# nigme3_Potentiom_tres.net
KiCad netlist of a schematic drawn in Altium Designer
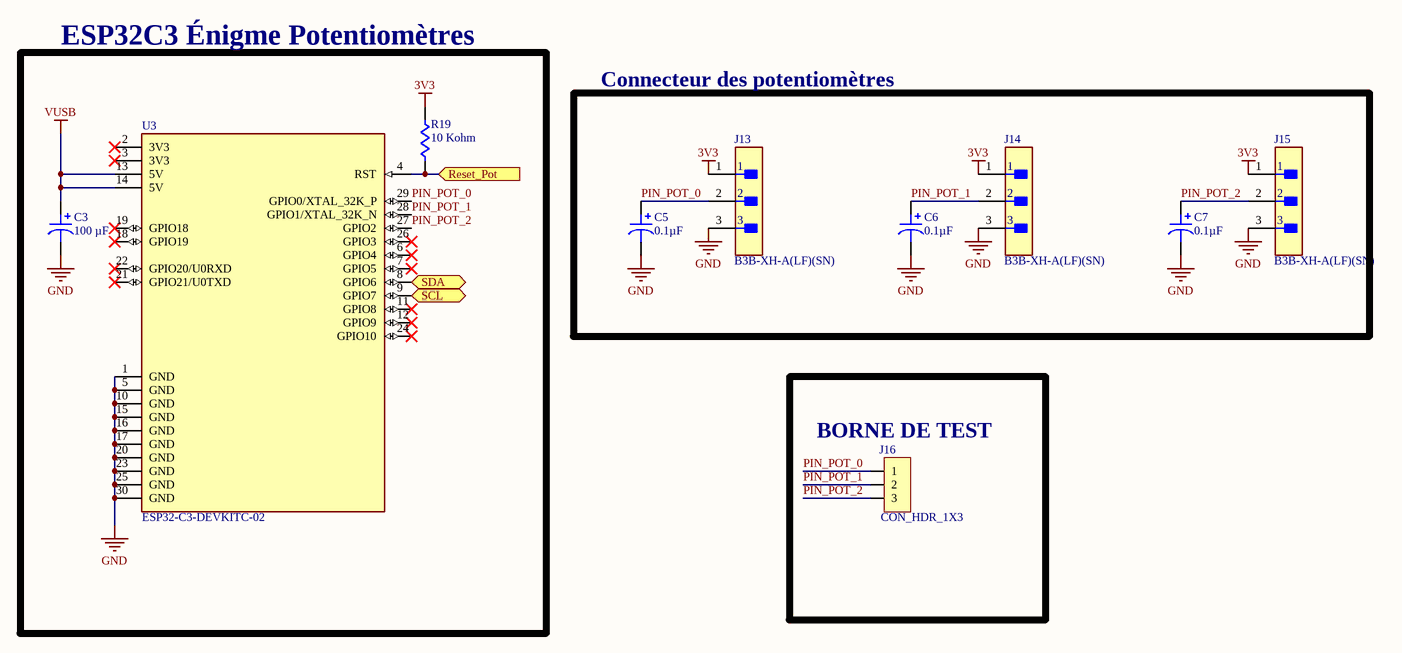
[diagram p0: Énigme3_Potentiomètres.SchDoc]

(export (version "E")
  (design (tool "Eeschema 10.0.6"))
  (components
    (comp (ref "C3")
      (value "100 µF")
      (footprint "CAP AL TH D8 L3.5 H12.5")
      (description "CAP ALUM 100UF 20% 50V RADIAL")
      (fields (field (name "PART NUMBER") "860020674015") (field (name "MANUFACTURER") "Würth Elektronik"))
      (libsource (lib "Celestial Altium Library - altium_library") (part "Polarised Capacitor"))
    )
    (comp (ref "C5")
      (value "0.1µF")
      (footprint "CAP TH ALUM ELEC D5.00mm S2.00mm H12.00mm")
      (description "CAP ALUM 0.1UF 10% 100V RADIAL")
      (fields (field (name "PART NUMBER") "UKL2A0R1KDD") (field (name "MANUFACTURER") "Nichicon"))
      (libsource (lib "Celestial Altium Library - altium_library") (part "Polarised Capacitor"))
    )
    (comp (ref "C6")
      (value "0.1µF")
      (footprint "CAP TH ALUM ELEC D5.00mm S2.00mm H12.00mm")
      (description "CAP ALUM 0.1UF 10% 100V RADIAL")
      (fields (field (name "PART NUMBER") "UKL2A0R1KDD") (field (name "MANUFACTURER") "Nichicon"))
      (libsource (lib "Celestial Altium Library - altium_library") (part "Polarised Capacitor"))
    )
    (comp (ref "C7")
      (value "0.1µF")
      (footprint "CAP TH ALUM ELEC D5.00mm S2.00mm H12.00mm")
      (description "CAP ALUM 0.1UF 10% 100V RADIAL")
      (fields (field (name "PART NUMBER") "UKL2A0R1KDD") (field (name "MANUFACTURER") "Nichicon"))
      (libsource (lib "Celestial Altium Library - altium_library") (part "Polarised Capacitor"))
    )
    (comp (ref "J13")
      (value "B3B-XH-A(LF)(SN)")
      (footprint "FP-B3B-XH-A_LF_SN-MFG")
      (description "CONN HEADER VERT 3POS 2.5MM")
      (libsource (lib "Altium Content Vault") (part "0d3f023dd272f625e17a2be33dea85f"))
    )
    (comp (ref "J14")
      (value "B3B-XH-A(LF)(SN)")
      (footprint "FP-B3B-XH-A_LF_SN-MFG")
      (description "CONN HEADER VERT 3POS 2.5MM")
      (libsource (lib "Altium Content Vault") (part "0d3f023dd272f625e17a2be33dea85f"))
    )
    (comp (ref "J15")
      (value "B3B-XH-A(LF)(SN)")
      (footprint "FP-B3B-XH-A_LF_SN-MFG")
      (description "CONN HEADER VERT 3POS 2.5MM")
      (libsource (lib "Altium Content Vault") (part "0d3f023dd272f625e17a2be33dea85f"))
    )
    (comp (ref "J16")
      (value "CON_HDR_1X3")
      (footprint "CON_HDR_1x3")
      (description "CON - Header 1x3 pins-100Mils - TH")
      (fields (field (name "SOURCE") "CEGEP_SHERBROOKE_TGE_LIBRARY.SchLib"))
      (libsource (lib "Cegep de Sherbrooke") (part "CON_HDR_1X3"))
    )
    (comp (ref "R19")
      (value "10 Kohm")
      (footprint "Res_Template")
      (description "Custom Semiconductor Resistor")
      (libsource (lib "Schlib1") (part "470 ohm"))
    )
    (comp (ref "U3")
      (value "ESP32-C3-DEVKITC-02")
      (footprint "XCVR_ESP32-C3-DEVKITC-02")
      (fields (field (name "MP") "ESP32-C3-DevKitC-02") (field (name "MF") "Espressif Systems"))
      (libsource (lib "ESP32-C3-DEVKITC-02") (part "ESP32-C3-DEVKITC-02"))
    )
  )
  (nets
    (net (code "1") (name "/PIN_POT_0") (class "Default")
      (node (ref "C5") (pin "1") (pinfunction "1_1") (pintype "passive"))
      (node (ref "J13") (pin "2") (pinfunction "2_2") (pintype "passive"))
      (node (ref "J16") (pin "1") (pinfunction "1_1") (pintype "passive"))
      (node (ref "U3") (pin "29") (pinfunction "GPIO0/XTAL_32K_P_29") (pintype "bidirectional"))
    )
    (net (code "2") (name "/PIN_POT_1") (class "Default")
      (node (ref "C6") (pin "1") (pinfunction "1_1") (pintype "passive"))
      (node (ref "J14") (pin "2") (pinfunction "2_2") (pintype "passive"))
      (node (ref "J16") (pin "2") (pinfunction "2_2") (pintype "passive"))
      (node (ref "U3") (pin "28") (pinfunction "GPIO1/XTAL_32K_N_28") (pintype "bidirectional"))
    )
    (net (code "3") (name "/PIN_POT_2") (class "Default")
      (node (ref "C7") (pin "1") (pinfunction "1_1") (pintype "passive"))
      (node (ref "J15") (pin "2") (pinfunction "2_2") (pintype "passive"))
      (node (ref "J16") (pin "3") (pinfunction "3_3") (pintype "passive"))
      (node (ref "U3") (pin "27") (pinfunction "GPIO2_27") (pintype "bidirectional"))
    )
    (net (code "4") (name "/Reset_Pot") (class "Default")
      (node (ref "R19") (pin "1") (pinfunction "1_1") (pintype "passive"))
      (node (ref "U3") (pin "4") (pinfunction "RST_4") (pintype "input"))
    )
    (net (code "5") (name "/SCL") (class "Default")
      (node (ref "U3") (pin "9") (pinfunction "GPIO7_9") (pintype "bidirectional"))
    )
    (net (code "6") (name "/SDA") (class "Default")
      (node (ref "U3") (pin "8") (pinfunction "GPIO6_8") (pintype "bidirectional"))
    )
    (net (code "7") (name "3V3") (class "Default")
      (node (ref "J13") (pin "1") (pinfunction "1_1") (pintype "passive"))
      (node (ref "J14") (pin "1") (pinfunction "1_1") (pintype "passive"))
      (node (ref "J15") (pin "1") (pinfunction "1_1") (pintype "passive"))
      (node (ref "R19") (pin "2") (pinfunction "2_2") (pintype "passive"))
    )
    (net (code "8") (name "GND") (class "Default")
      (node (ref "C3") (pin "2") (pinfunction "2_2") (pintype "passive"))
      (node (ref "C5") (pin "2") (pinfunction "2_2") (pintype "passive"))
      (node (ref "C6") (pin "2") (pinfunction "2_2") (pintype "passive"))
      (node (ref "C7") (pin "2") (pinfunction "2_2") (pintype "passive"))
      (node (ref "J13") (pin "3") (pinfunction "3_3") (pintype "passive"))
      (node (ref "J14") (pin "3") (pinfunction "3_3") (pintype "passive"))
      (node (ref "J15") (pin "3") (pinfunction "3_3") (pintype "passive"))
      (node (ref "U3") (pin "1") (pinfunction "GND_1") (pintype "power_in"))
      (node (ref "U3") (pin "10") (pinfunction "GND_10") (pintype "power_in"))
      (node (ref "U3") (pin "15") (pinfunction "GND_15") (pintype "power_in"))
      (node (ref "U3") (pin "16") (pinfunction "GND_16") (pintype "power_in"))
      (node (ref "U3") (pin "17") (pinfunction "GND_17") (pintype "power_in"))
      (node (ref "U3") (pin "20") (pinfunction "GND_20") (pintype "power_in"))
      (node (ref "U3") (pin "23") (pinfunction "GND_23") (pintype "power_in"))
      (node (ref "U3") (pin "25") (pinfunction "GND_25") (pintype "power_in"))
      (node (ref "U3") (pin "30") (pinfunction "GND_30") (pintype "power_in"))
      (node (ref "U3") (pin "5") (pinfunction "GND_5") (pintype "power_in"))
    )
    (net (code "9") (name "VUSB") (class "Default")
      (node (ref "C3") (pin "1") (pinfunction "1_1") (pintype "passive"))
      (node (ref "U3") (pin "13") (pinfunction "5V_13") (pintype "power_in"))
      (node (ref "U3") (pin "14") (pinfunction "5V_14") (pintype "power_in"))
    )
    (net (code "10") (name "unconnected-(U3-3V3-Pad2)") (class "Default")
      (node (ref "U3") (pin "2") (pinfunction "3V3_2") (pintype "power_in+no_connect"))
    )
    (net (code "11") (name "unconnected-(U3-3V3-Pad3)") (class "Default")
      (node (ref "U3") (pin "3") (pinfunction "3V3_3") (pintype "power_in+no_connect"))
    )
    (net (code "12") (name "unconnected-(U3-GPIO3-Pad26)") (class "Default")
      (node (ref "U3") (pin "26") (pinfunction "GPIO3_26") (pintype "bidirectional+no_connect"))
    )
    (net (code "13") (name "unconnected-(U3-GPIO4-Pad6)") (class "Default")
      (node (ref "U3") (pin "6") (pinfunction "GPIO4_6") (pintype "bidirectional+no_connect"))
    )
    (net (code "14") (name "unconnected-(U3-GPIO5-Pad7)") (class "Default")
      (node (ref "U3") (pin "7") (pinfunction "GPIO5_7") (pintype "bidirectional+no_connect"))
    )
    (net (code "15") (name "unconnected-(U3-GPIO8-Pad11)") (class "Default")
      (node (ref "U3") (pin "11") (pinfunction "GPIO8_11") (pintype "bidirectional+no_connect"))
    )
    (net (code "16") (name "unconnected-(U3-GPIO9-Pad12)") (class "Default")
      (node (ref "U3") (pin "12") (pinfunction "GPIO9_12") (pintype "bidirectional+no_connect"))
    )
    (net (code "17") (name "unconnected-(U3-GPIO10-Pad24)") (class "Default")
      (node (ref "U3") (pin "24") (pinfunction "GPIO10_24") (pintype "bidirectional+no_connect"))
    )
    (net (code "18") (name "unconnected-(U3-GPIO18-Pad19)") (class "Default")
      (node (ref "U3") (pin "19") (pinfunction "GPIO18_19") (pintype "bidirectional+no_connect"))
    )
    (net (code "19") (name "unconnected-(U3-GPIO19-Pad18)") (class "Default")
      (node (ref "U3") (pin "18") (pinfunction "GPIO19_18") (pintype "bidirectional+no_connect"))
    )
    (net (code "20") (name "unconnected-(U3-GPIO20{slash}U0RXD-Pad22)") (class "Default")
      (node (ref "U3") (pin "22") (pinfunction "GPIO20/U0RXD_22") (pintype "bidirectional+no_connect"))
    )
    (net (code "21") (name "unconnected-(U3-GPIO21{slash}U0TXD-Pad21)") (class "Default")
      (node (ref "U3") (pin "21") (pinfunction "GPIO21/U0TXD_21") (pintype "bidirectional+no_connect"))
    )
  )
)
